# 1wireESP.net
KiCad netlist of a schematic drawn in EAGLE
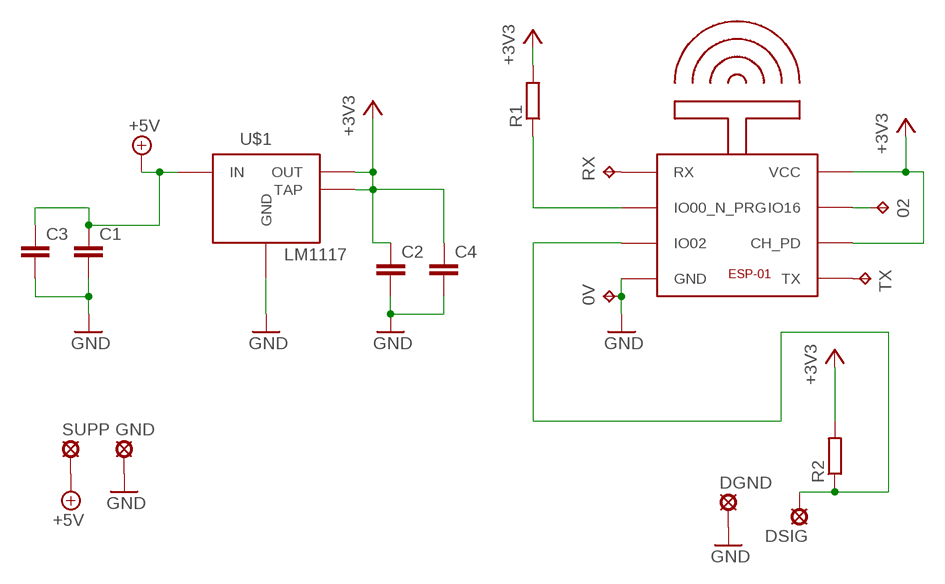
[diagram p0: schematic, sheet 1]

(export (version "E")
  (design (tool "Eeschema 10.0.6"))
  (components
    (comp (ref "0V")
      (value "TPB2,54")
      (footprint "eagle-import:B2,54")
      (libsource (lib "eagle-import") (part "TPB2,54"))
    )
    (comp (ref "02")
      (value "TPB2,54")
      (footprint "eagle-import:B2,54")
      (libsource (lib "eagle-import") (part "TPB2,54"))
    )
    (comp (ref "C1")
      (value "C-EUC0603K")
      (footprint "eagle-import:C0603K")
      (libsource (lib "eagle-import") (part "C-EUC0603K"))
    )
    (comp (ref "C2")
      (value "C-EUC0603K")
      (footprint "eagle-import:C0603K")
      (libsource (lib "eagle-import") (part "C-EUC0603K"))
    )
    (comp (ref "C3")
      (value "C-EUC0805K")
      (footprint "eagle-import:C0805K")
      (libsource (lib "eagle-import") (part "C-EUC0805K"))
    )
    (comp (ref "C4")
      (value "C-EUC0805K")
      (footprint "eagle-import:C0805K")
      (libsource (lib "eagle-import") (part "C-EUC0805K"))
    )
    (comp (ref "DGND")
      (value "LSP10")
      (footprint "eagle-import:LSP10")
      (libsource (lib "eagle-import") (part "LSP10"))
    )
    (comp (ref "DSIG")
      (value "LSP10")
      (footprint "eagle-import:LSP10")
      (libsource (lib "eagle-import") (part "LSP10"))
    )
    (comp (ref "GND")
      (value "LSP10")
      (footprint "eagle-import:LSP10")
      (libsource (lib "eagle-import") (part "LSP10"))
    )
    (comp (ref "R1")
      (value "R-EU_R0603")
      (footprint "eagle-import:R0603")
      (libsource (lib "eagle-import") (part "R-EU_R0603"))
    )
    (comp (ref "R2")
      (value "R-EU_R0603")
      (footprint "eagle-import:R0603")
      (libsource (lib "eagle-import") (part "R-EU_R0603"))
    )
    (comp (ref "RX")
      (value "TPB2,54")
      (footprint "eagle-import:B2,54")
      (libsource (lib "eagle-import") (part "TPB2,54"))
    )
    (comp (ref "SUPP")
      (value "LSP10")
      (footprint "eagle-import:LSP10")
      (libsource (lib "eagle-import") (part "LSP10"))
    )
    (comp (ref "TX")
      (value "TPB2,54")
      (footprint "eagle-import:B2,54")
      (libsource (lib "eagle-import") (part "TPB2,54"))
    )
    (comp (ref "U$1")
      (value "LM1117")
      (footprint "eagle-import:SOT223")
      (libsource (lib "eagle-import") (part "LM1117"))
    )
    (comp (ref "U$2")
      (value "ESP-01")
      (footprint "eagle-import:ESP-01")
      (libsource (lib "eagle-import") (part "ESP-01"))
    )
  )
  (nets
    (net (code "1") (name "+3V3") (class "Default")
      (node (ref "C2") (pin "1") (pinfunction "1_1") (pintype "passive"))
      (node (ref "C4") (pin "1") (pinfunction "1_1") (pintype "passive"))
      (node (ref "R1") (pin "2") (pinfunction "2_2") (pintype "passive"))
      (node (ref "R2") (pin "2") (pinfunction "2_2") (pintype "passive"))
      (node (ref "U$1") (pin "MID") (pinfunction "OUT_MID") (pintype "bidirectional"))
      (node (ref "U$1") (pin "TAP") (pinfunction "TAP_TAP") (pintype "bidirectional"))
      (node (ref "U$2") (pin "CH_PD") (pinfunction "CH_PD_CH_PD") (pintype "bidirectional"))
      (node (ref "U$2") (pin "VCC") (pinfunction "VCC_VCC") (pintype "bidirectional"))
    )
    (net (code "2") (name "+5V") (class "Default")
      (node (ref "C1") (pin "1") (pinfunction "1_1") (pintype "passive"))
      (node (ref "C3") (pin "1") (pinfunction "1_1") (pintype "passive"))
      (node (ref "SUPP") (pin "MP") (pinfunction "MP_MP") (pintype "passive"))
      (node (ref "U$1") (pin "RIGHT") (pinfunction "IN_RIGHT") (pintype "bidirectional"))
    )
    (net (code "3") (name "GND") (class "Default")
      (node (ref "0V") (pin "TP") (pinfunction "TP_TP") (pintype "input"))
      (node (ref "C1") (pin "2") (pinfunction "2_2") (pintype "passive"))
      (node (ref "C2") (pin "2") (pinfunction "2_2") (pintype "passive"))
      (node (ref "C3") (pin "2") (pinfunction "2_2") (pintype "passive"))
      (node (ref "C4") (pin "2") (pinfunction "2_2") (pintype "passive"))
      (node (ref "DGND") (pin "MP") (pinfunction "MP_MP") (pintype "passive"))
      (node (ref "GND") (pin "MP") (pinfunction "MP_MP") (pintype "passive"))
      (node (ref "U$1") (pin "LEFT") (pinfunction "GND_LEFT") (pintype "bidirectional"))
      (node (ref "U$2") (pin "GND") (pinfunction "GND_GND") (pintype "bidirectional"))
    )
    (net (code "4") (name "Net-(RX-PadTP)") (class "Default")
      (node (ref "RX") (pin "TP") (pinfunction "TP_TP") (pintype "input"))
      (node (ref "U$2") (pin "RX") (pinfunction "RX_RX") (pintype "bidirectional"))
    )
    (net (code "5") (name "Net-(TX-PadTP)") (class "Default")
      (node (ref "TX") (pin "TP") (pinfunction "TP_TP") (pintype "input"))
      (node (ref "U$2") (pin "TX") (pinfunction "TX_TX") (pintype "bidirectional"))
    )
    (net (code "6") (name "Net-(U$2-IO00_N_PRG)") (class "Default")
      (node (ref "R1") (pin "1") (pinfunction "1_1") (pintype "passive"))
      (node (ref "U$2") (pin "GPIO0_N_PROG") (pinfunction "IO00_N_PRG_GPIO0_N_PROG") (pintype "bidirectional"))
    )
    (net (code "7") (name "Net-(U$2-IO02)") (class "Default")
      (node (ref "DSIG") (pin "MP") (pinfunction "MP_MP") (pintype "passive"))
      (node (ref "R2") (pin "1") (pinfunction "1_1") (pintype "passive"))
      (node (ref "U$2") (pin "GPIO02") (pinfunction "IO02_GPIO02") (pintype "bidirectional"))
    )
    (net (code "8") (name "Net-(U$2-IO16)") (class "Default")
      (node (ref "02") (pin "TP") (pinfunction "TP_TP") (pintype "input"))
      (node (ref "U$2") (pin "GPIO16") (pinfunction "IO16_GPIO16") (pintype "bidirectional"))
    )
  )
)
